# Power.net
KiCad netlist of a schematic drawn in Altium Designer
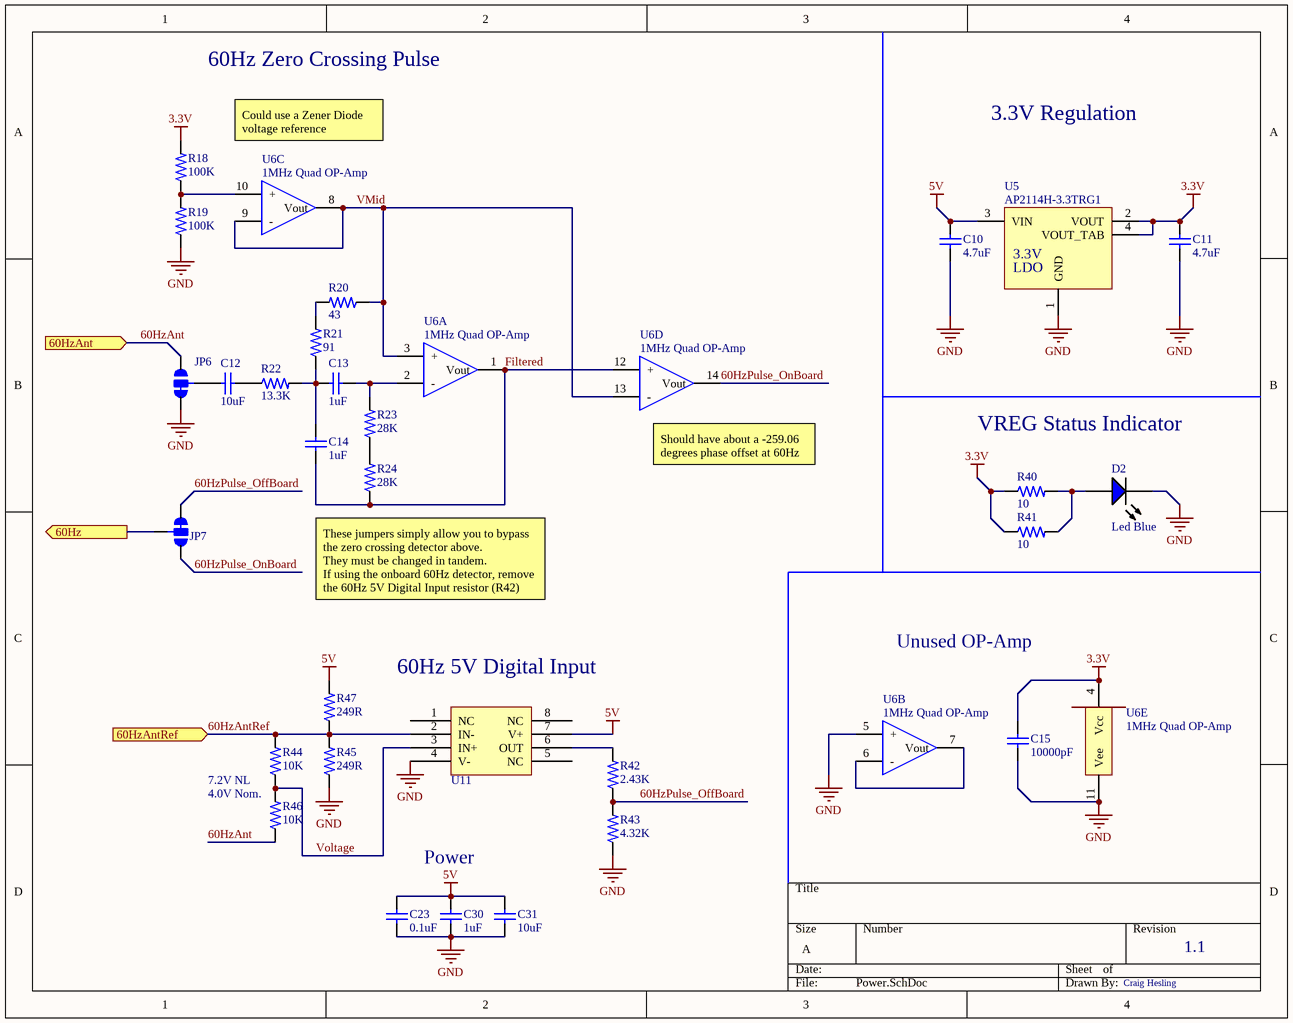
[diagram p0: Power.SchDoc]

(export (version "E")
  (design (tool "Eeschema 10.0.6"))
  (components
    (comp (ref "C10")
      (value "4.7uF")
      (footprint "CAPC3216X18L - CAP1206 1.8MM TALL")
      (description "SMT 1206 Ceramic Capacitor")
      (fields (field (name "TOLERANCE") "10%") (field (name "VOLTAGE") "25V"))
      (libsource (lib "Passives") (part "CAP1206 4.7uF 10% 25V X5R"))
    )
    (comp (ref "C11")
      (value "4.7uF")
      (footprint "CAPC3216X18L - CAP1206 1.8MM TALL")
      (description "SMT 1206 Ceramic Capacitor")
      (fields (field (name "TOLERANCE") "10%") (field (name "VOLTAGE") "25V"))
      (libsource (lib "Passives") (part "CAP1206 4.7uF 10% 25V X5R"))
    )
    (comp (ref "C12")
      (value "10uF")
      (footprint "CAPC1608X09L - CAP0603")
      (description "SMT 0603 Ceramic Capacitor")
      (fields (field (name "TOLERANCE") "20%") (field (name "VOLTAGE") "6.3V"))
      (libsource (lib "Passives") (part "CAP0603 10uF 20% 6.3V X5R"))
    )
    (comp (ref "C13")
      (value "1uF")
      (footprint "CAPC1608X09L - CAP0603")
      (description "SMT 0603 Ceramic Capacitor")
      (fields (field (name "TOLERANCE") "10%") (field (name "VOLTAGE") "10V"))
      (libsource (lib "Passives") (part "CAP0603 1uF 10% 10V X7R"))
    )
    (comp (ref "C14")
      (value "1uF")
      (footprint "CAPC1608X09L - CAP0603")
      (description "SMT 0603 Ceramic Capacitor")
      (fields (field (name "TOLERANCE") "10%") (field (name "VOLTAGE") "10V"))
      (libsource (lib "Passives") (part "CAP0603 1uF 10% 10V X7R"))
    )
    (comp (ref "C15")
      (value "10000pF")
      (footprint "CAPC1608X09L - CAP0603")
      (description "SMT 0603 Ceramic Capacitor")
      (fields (field (name "TOLERANCE") "10%") (field (name "VOLTAGE") "50V"))
      (libsource (lib "Passives") (part "CAP0603 10000pF 10% 50V X7R"))
    )
    (comp (ref "C23")
      (value "0.1uF")
      (footprint "CAPC1608X09L - CAP0603")
      (description "SMT 0603 Ceramic Capacitor")
      (fields (field (name "TOLERANCE") "10%") (field (name "VOLTAGE") "25V"))
      (libsource (lib "Passives") (part "CAP0603 0.1uF 10% 25V X7R"))
    )
    (comp (ref "C30")
      (value "1uF")
      (footprint "CAPC1608X09L - CAP0603")
      (description "SMT 0603 Ceramic Capacitor")
      (fields (field (name "TOLERANCE") "10%") (field (name "VOLTAGE") "10V"))
      (libsource (lib "Passives") (part "CAP0603 1uF 10% 10V X7R"))
    )
    (comp (ref "C31")
      (value "10uF")
      (footprint "CAPC1608X09L - CAP0603")
      (description "SMT 0603 Ceramic Capacitor")
      (fields (field (name "TOLERANCE") "20%") (field (name "VOLTAGE") "6.3V"))
      (libsource (lib "Passives") (part "CAP0603 10uF 20% 6.3V X5R"))
    )
    (comp (ref "D2")
      (value "Led Blue")
      (footprint "LED-0603-BLUE .7MM TALL")
      (description "LED BLUE CLEAR 0603 SMD 145 mcd")
      (libsource (lib "Actives") (part "LED0603 BLUE 20mA 250mcd"))
    )
    (comp (ref "JP6")
      (value "JUMPER-PAD-3-2OF3_NC_BY_TRACE_SMALL")
      (footprint "PAD-JUMPER-3-2OF3_NC_BY_TRACE_YES_SILK_FULL_BOX")
      (libsource (lib "") (part "JUMPER-PAD-3-2OF3_NC_BY_TRACE_SMALL_1"))
    )
    (comp (ref "JP7")
      (value "JUMPER-PAD-3-2OF3_NC_BY_TRACE_SMALL")
      (footprint "PAD-JUMPER-3-2OF3_NC_BY_TRACE_YES_SILK_FULL_BOX")
      (libsource (lib "Passives") (part "JUMPER-PAD-3-2OF3_NC_BY_TRACE_SMALL"))
    )
    (comp (ref "R18")
      (value "100K")
      (footprint "RESC1608X06L - RES0603")
      (description "SMT 0603 Ceramic Resistor")
      (fields (field (name "POWER") "1/10W") (field (name "TOLERANCE") "1%"))
      (libsource (lib "Passives") (part "RES0603 100K 1% 1/10W"))
    )
    (comp (ref "R19")
      (value "100K")
      (footprint "RESC1608X06L - RES0603")
      (description "SMT 0603 Ceramic Resistor")
      (fields (field (name "POWER") "1/10W") (field (name "TOLERANCE") "1%"))
      (libsource (lib "Passives") (part "RES0603 100K 1% 1/10W"))
    )
    (comp (ref "R20")
      (value "43")
      (footprint "RESC1608X06L - RES0603")
      (description "SMT 0603 Ceramic Resistor")
      (fields (field (name "POWER") "1/10W") (field (name "TOLERANCE") "1%"))
      (libsource (lib "Passives") (part "RES0603 43 1% 1/10W"))
    )
    (comp (ref "R21")
      (value "91")
      (footprint "RESC1608X06L - RES0603")
      (description "SMT 0603 Ceramic Resistor")
      (fields (field (name "POWER") "1/10W") (field (name "TOLERANCE") "1%"))
      (libsource (lib "Passives") (part "RES0603 91 1% 1/10W"))
    )
    (comp (ref "R22")
      (value "13.3K")
      (footprint "RESC1608X06L - RES0603")
      (description "SMT 0603 Ceramic Resistor")
      (fields (field (name "POWER") "1/10W") (field (name "TOLERANCE") "1%"))
      (libsource (lib "Passives") (part "RES0603 13.3K 1% 1/10W"))
    )
    (comp (ref "R23")
      (value "28K")
      (footprint "RESC1608X06L - RES0603")
      (description "SMT 0603 Ceramic Resistor")
      (fields (field (name "POWER") "1/10W") (field (name "TOLERANCE") "0.1%"))
      (libsource (lib "Passives") (part "RES0603 28K 0.1% 1/10W"))
    )
    (comp (ref "R24")
      (value "28K")
      (footprint "RESC1608X06L - RES0603")
      (description "SMT 0603 Ceramic Resistor")
      (fields (field (name "POWER") "1/10W") (field (name "TOLERANCE") "0.1%"))
      (libsource (lib "Passives") (part "RES0603 28K 0.1% 1/10W"))
    )
    (comp (ref "R40")
      (value "10")
      (footprint "RESC1608X06L - RES0603")
      (description "SMT 0603 Ceramic Resistor")
      (fields (field (name "POWER") "1/10W") (field (name "TOLERANCE") "1%"))
      (libsource (lib "Passives") (part "RES0603 10 1% 1/10W"))
    )
    (comp (ref "R41")
      (value "10")
      (footprint "RESC1608X06L - RES0603")
      (description "SMT 0603 Ceramic Resistor")
      (fields (field (name "POWER") "1/10W") (field (name "TOLERANCE") "1%"))
      (libsource (lib "Passives") (part "RES0603 10 1% 1/10W"))
    )
    (comp (ref "R42")
      (value "2.43K")
      (footprint "RESC1608X06L - RES0603")
      (description "SMT 0603 Ceramic Resistor")
      (fields (field (name "POWER") "1/10W") (field (name "TOLERANCE") "1%"))
      (libsource (lib "Passives") (part "RES0603 2.43K 1% 1/10W"))
    )
    (comp (ref "R43")
      (value "4.32K")
      (footprint "RESC1608X06L - RES0603")
      (description "SMT 0603 Ceramic Resistor")
      (fields (field (name "POWER") "1/10W") (field (name "TOLERANCE") "1%"))
      (libsource (lib "Passives") (part "RES0603 4.32K 1% 1/10W"))
    )
    (comp (ref "R44")
      (value "10K")
      (footprint "RESC1608X06L - RES0603")
      (description "SMT 0603 Ceramic Resistor")
      (fields (field (name "POWER") "1/10W") (field (name "TOLERANCE") "1%"))
      (libsource (lib "Passives") (part "RES0603 10K 1% 1/10W"))
    )
    (comp (ref "R45")
      (value "249R")
      (footprint "RESC1608X06L - RES0603")
      (description "RES SMD 249 OHM 1% 1/10W 0603")
      (fields
        (field (name "MANUFACTURER") "Yageo")
        (field (name "MANUFACTURER PART NUMBER") "RC0603FR-07249RL")
      )
      (libsource (lib "Passives") (part "RC0603FR-07249RL"))
    )
    (comp (ref "R46")
      (value "10K")
      (footprint "RESC1608X06L - RES0603")
      (description "SMT 0603 Ceramic Resistor")
      (fields (field (name "POWER") "1/10W") (field (name "TOLERANCE") "1%"))
      (libsource (lib "Passives") (part "RES0603 10K 1% 1/10W"))
    )
    (comp (ref "R47")
      (value "249R")
      (footprint "RESC1608X06L - RES0603")
      (description "RES SMD 249 OHM 1% 1/10W 0603")
      (fields
        (field (name "MANUFACTURER") "Yageo")
        (field (name "MANUFACTURER PART NUMBER") "RC0603FR-07249RL")
      )
      (libsource (lib "Passives") (part "RC0603FR-07249RL"))
    )
    (comp (ref "U5")
      (value "AP2114H-3.3TRG1")
      (footprint "SOT230P700X180-4L")
      (description "AP2114 3.3V Fixed LDO Regulator")
      (libsource (lib "Actives") (part "AP2114H-3.3TRG1"))
    )
    (comp (ref "U6")
      (value "1MHz Quad OP-Amp")
      (footprint "SOIC127P600X175-14L")
      (description "ON Semi LM324DR2G 1MHz Quad OP-Amp")
      (libsource (lib "Actives") (part "LM324DR2G"))
    )
    (comp (ref "U11")
      (value "LT1818IS8#PBF")
      (footprint "SOIC127P600X175-8N")
      (description "IC OPAMP VFB 400MHZ 8SO")
      (fields (field (name "MANUFACTURER") "Linear Technology"))
      (libsource (lib "Actives") (part "LT1818IS8#PBF"))
    )
  )
  (nets
    (net (code "1") (name "/60Hz") (class "Default")
      (node (ref "JP7") (pin "2") (pinfunction "2_2") (pintype "passive"))
    )
    (net (code "2") (name "/60HzAnt") (class "Default")
      (node (ref "JP6") (pin "1") (pinfunction "1_1") (pintype "passive"))
      (node (ref "R46") (pin "1") (pinfunction "1_1") (pintype "passive"))
    )
    (net (code "3") (name "/60HzAntRef") (class "Default")
      (node (ref "R44") (pin "2") (pinfunction "2_2") (pintype "passive"))
      (node (ref "R45") (pin "2") (pinfunction "2_2") (pintype "passive"))
      (node (ref "R47") (pin "1") (pinfunction "1_1") (pintype "passive"))
      (node (ref "U11") (pin "2") (pinfunction "IN-_2") (pintype "passive"))
    )
    (net (code "4") (name "/60HzPulse_OffBoard") (class "Default")
      (node (ref "JP7") (pin "3") (pinfunction "3_3") (pintype "passive"))
      (node (ref "R42") (pin "1") (pinfunction "1_1") (pintype "passive"))
      (node (ref "R43") (pin "2") (pinfunction "2_2") (pintype "passive"))
    )
    (net (code "5") (name "/60HzPulse_OnBoard") (class "Default")
      (node (ref "JP7") (pin "1") (pinfunction "1_1") (pintype "passive"))
      (node (ref "U6") (pin "14") (pinfunction "Vout_14") (pintype "passive"))
    )
    (net (code "6") (name "/Filtered") (class "Default")
      (node (ref "C14") (pin "1") (pinfunction "1_1") (pintype "passive"))
      (node (ref "R24") (pin "1") (pinfunction "1_1") (pintype "passive"))
      (node (ref "U6") (pin "1") (pinfunction "Vout_1") (pintype "passive"))
      (node (ref "U6") (pin "12") (pinfunction "+_12") (pintype "passive"))
    )
    (net (code "7") (name "/VMid") (class "Default")
      (node (ref "R20") (pin "1") (pinfunction "1_1") (pintype "passive"))
      (node (ref "U6") (pin "13") (pinfunction "-_13") (pintype "passive"))
      (node (ref "U6") (pin "3") (pinfunction "+_3") (pintype "passive"))
      (node (ref "U6") (pin "8") (pinfunction "Vout_8") (pintype "passive"))
      (node (ref "U6") (pin "9") (pinfunction "-_9") (pintype "passive"))
    )
    (net (code "8") (name "/Voltage") (class "Default")
      (node (ref "R44") (pin "1") (pinfunction "1_1") (pintype "passive"))
      (node (ref "R46") (pin "2") (pinfunction "2_2") (pintype "passive"))
      (node (ref "U11") (pin "3") (pinfunction "IN+_3") (pintype "passive"))
    )
    (net (code "9") (name "3.3V") (class "Default")
      (node (ref "C11") (pin "2") (pinfunction "2_2") (pintype "passive"))
      (node (ref "C15") (pin "2") (pinfunction "2_2") (pintype "passive"))
      (node (ref "R18") (pin "2") (pinfunction "2_2") (pintype "passive"))
      (node (ref "R40") (pin "1") (pinfunction "1_1") (pintype "passive"))
      (node (ref "R41") (pin "1") (pinfunction "1_1") (pintype "passive"))
      (node (ref "U5") (pin "2") (pinfunction "VOUT_2") (pintype "passive"))
      (node (ref "U5") (pin "4") (pinfunction "VOUT_TAB_4") (pintype "passive"))
      (node (ref "U6") (pin "4") (pinfunction "Vcc_4") (pintype "passive"))
    )
    (net (code "10") (name "5V") (class "Default")
      (node (ref "C10") (pin "2") (pinfunction "2_2") (pintype "passive"))
      (node (ref "C23") (pin "2") (pinfunction "2_2") (pintype "passive"))
      (node (ref "C30") (pin "2") (pinfunction "2_2") (pintype "passive"))
      (node (ref "C31") (pin "2") (pinfunction "2_2") (pintype "passive"))
      (node (ref "R47") (pin "2") (pinfunction "2_2") (pintype "passive"))
      (node (ref "U11") (pin "7") (pinfunction "V+_7") (pintype "passive"))
      (node (ref "U5") (pin "3") (pinfunction "VIN_3") (pintype "passive"))
    )
    (net (code "11") (name "GND") (class "Default")
      (node (ref "C10") (pin "1") (pinfunction "1_1") (pintype "passive"))
      (node (ref "C11") (pin "1") (pinfunction "1_1") (pintype "passive"))
      (node (ref "C15") (pin "1") (pinfunction "1_1") (pintype "passive"))
      (node (ref "C23") (pin "1") (pinfunction "1_1") (pintype "passive"))
      (node (ref "C30") (pin "1") (pinfunction "1_1") (pintype "passive"))
      (node (ref "C31") (pin "1") (pinfunction "1_1") (pintype "passive"))
      (node (ref "D2") (pin "K") (pinfunction "K_K") (pintype "passive"))
      (node (ref "JP6") (pin "3") (pinfunction "3_3") (pintype "passive"))
      (node (ref "R19") (pin "1") (pinfunction "1_1") (pintype "passive"))
      (node (ref "R43") (pin "1") (pinfunction "1_1") (pintype "passive"))
      (node (ref "R45") (pin "1") (pinfunction "1_1") (pintype "passive"))
      (node (ref "U11") (pin "4") (pinfunction "V-_4") (pintype "passive"))
      (node (ref "U5") (pin "1") (pinfunction "GND_1") (pintype "passive"))
      (node (ref "U6") (pin "11") (pinfunction "Vee_11") (pintype "passive"))
      (node (ref "U6") (pin "5") (pinfunction "+_5") (pintype "passive"))
    )
    (net (code "12") (name "Net-(C12-Pad1)") (class "Default")
      (node (ref "C12") (pin "1") (pinfunction "1_1") (pintype "passive"))
      (node (ref "R22") (pin "1") (pinfunction "1_1") (pintype "passive"))
    )
    (net (code "13") (name "Net-(C12-Pad2)") (class "Default")
      (node (ref "C12") (pin "2") (pinfunction "2_2") (pintype "passive"))
      (node (ref "JP6") (pin "2") (pinfunction "2_2") (pintype "passive"))
    )
    (net (code "14") (name "Net-(C13-Pad2)") (class "Default")
      (node (ref "C13") (pin "2") (pinfunction "2_2") (pintype "passive"))
      (node (ref "C14") (pin "2") (pinfunction "2_2") (pintype "passive"))
      (node (ref "R21") (pin "1") (pinfunction "1_1") (pintype "passive"))
      (node (ref "R22") (pin "2") (pinfunction "2_2") (pintype "passive"))
    )
    (net (code "15") (name "Net-(D2-PadA)") (class "Default")
      (node (ref "D2") (pin "A") (pinfunction "A_A") (pintype "passive"))
      (node (ref "R40") (pin "2") (pinfunction "2_2") (pintype "passive"))
      (node (ref "R41") (pin "2") (pinfunction "2_2") (pintype "passive"))
    )
    (net (code "16") (name "Net-(R20-Pad2)") (class "Default")
      (node (ref "R20") (pin "2") (pinfunction "2_2") (pintype "passive"))
      (node (ref "R21") (pin "2") (pinfunction "2_2") (pintype "passive"))
    )
    (net (code "17") (name "Net-(R23-Pad1)") (class "Default")
      (node (ref "R23") (pin "1") (pinfunction "1_1") (pintype "passive"))
      (node (ref "R24") (pin "2") (pinfunction "2_2") (pintype "passive"))
    )
    (net (code "18") (name "Net-(U6A--)") (class "Default")
      (node (ref "C13") (pin "1") (pinfunction "1_1") (pintype "passive"))
      (node (ref "R23") (pin "2") (pinfunction "2_2") (pintype "passive"))
      (node (ref "U6") (pin "2") (pinfunction "-_2") (pintype "passive"))
    )
    (net (code "19") (name "Net-(U6B--)") (class "Default")
      (node (ref "U6") (pin "6") (pinfunction "-_6") (pintype "passive"))
      (node (ref "U6") (pin "7") (pinfunction "Vout_7") (pintype "passive"))
    )
    (net (code "20") (name "Net-(U6C-+)") (class "Default")
      (node (ref "R18") (pin "1") (pinfunction "1_1") (pintype "passive"))
      (node (ref "R19") (pin "2") (pinfunction "2_2") (pintype "passive"))
      (node (ref "U6") (pin "10") (pinfunction "+_10") (pintype "passive"))
    )
    (net (code "21") (name "Net-(U11-OUT)") (class "Default")
      (node (ref "R42") (pin "2") (pinfunction "2_2") (pintype "passive"))
      (node (ref "U11") (pin "6") (pinfunction "OUT_6") (pintype "passive"))
    )
    (net (code "22") (name "unconnected-(U11-NC-Pad1)") (class "Default")
      (node (ref "U11") (pin "1") (pinfunction "NC_1") (pintype "passive"))
    )
    (net (code "23") (name "unconnected-(U11-NC-Pad5)") (class "Default")
      (node (ref "U11") (pin "5") (pinfunction "NC_5") (pintype "passive"))
    )
    (net (code "24") (name "unconnected-(U11-NC-Pad8)") (class "Default")
      (node (ref "U11") (pin "8") (pinfunction "NC_8") (pintype "passive"))
    )
  )
)
